# R204B.net
KiCad netlist of a schematic drawn in EAGLE
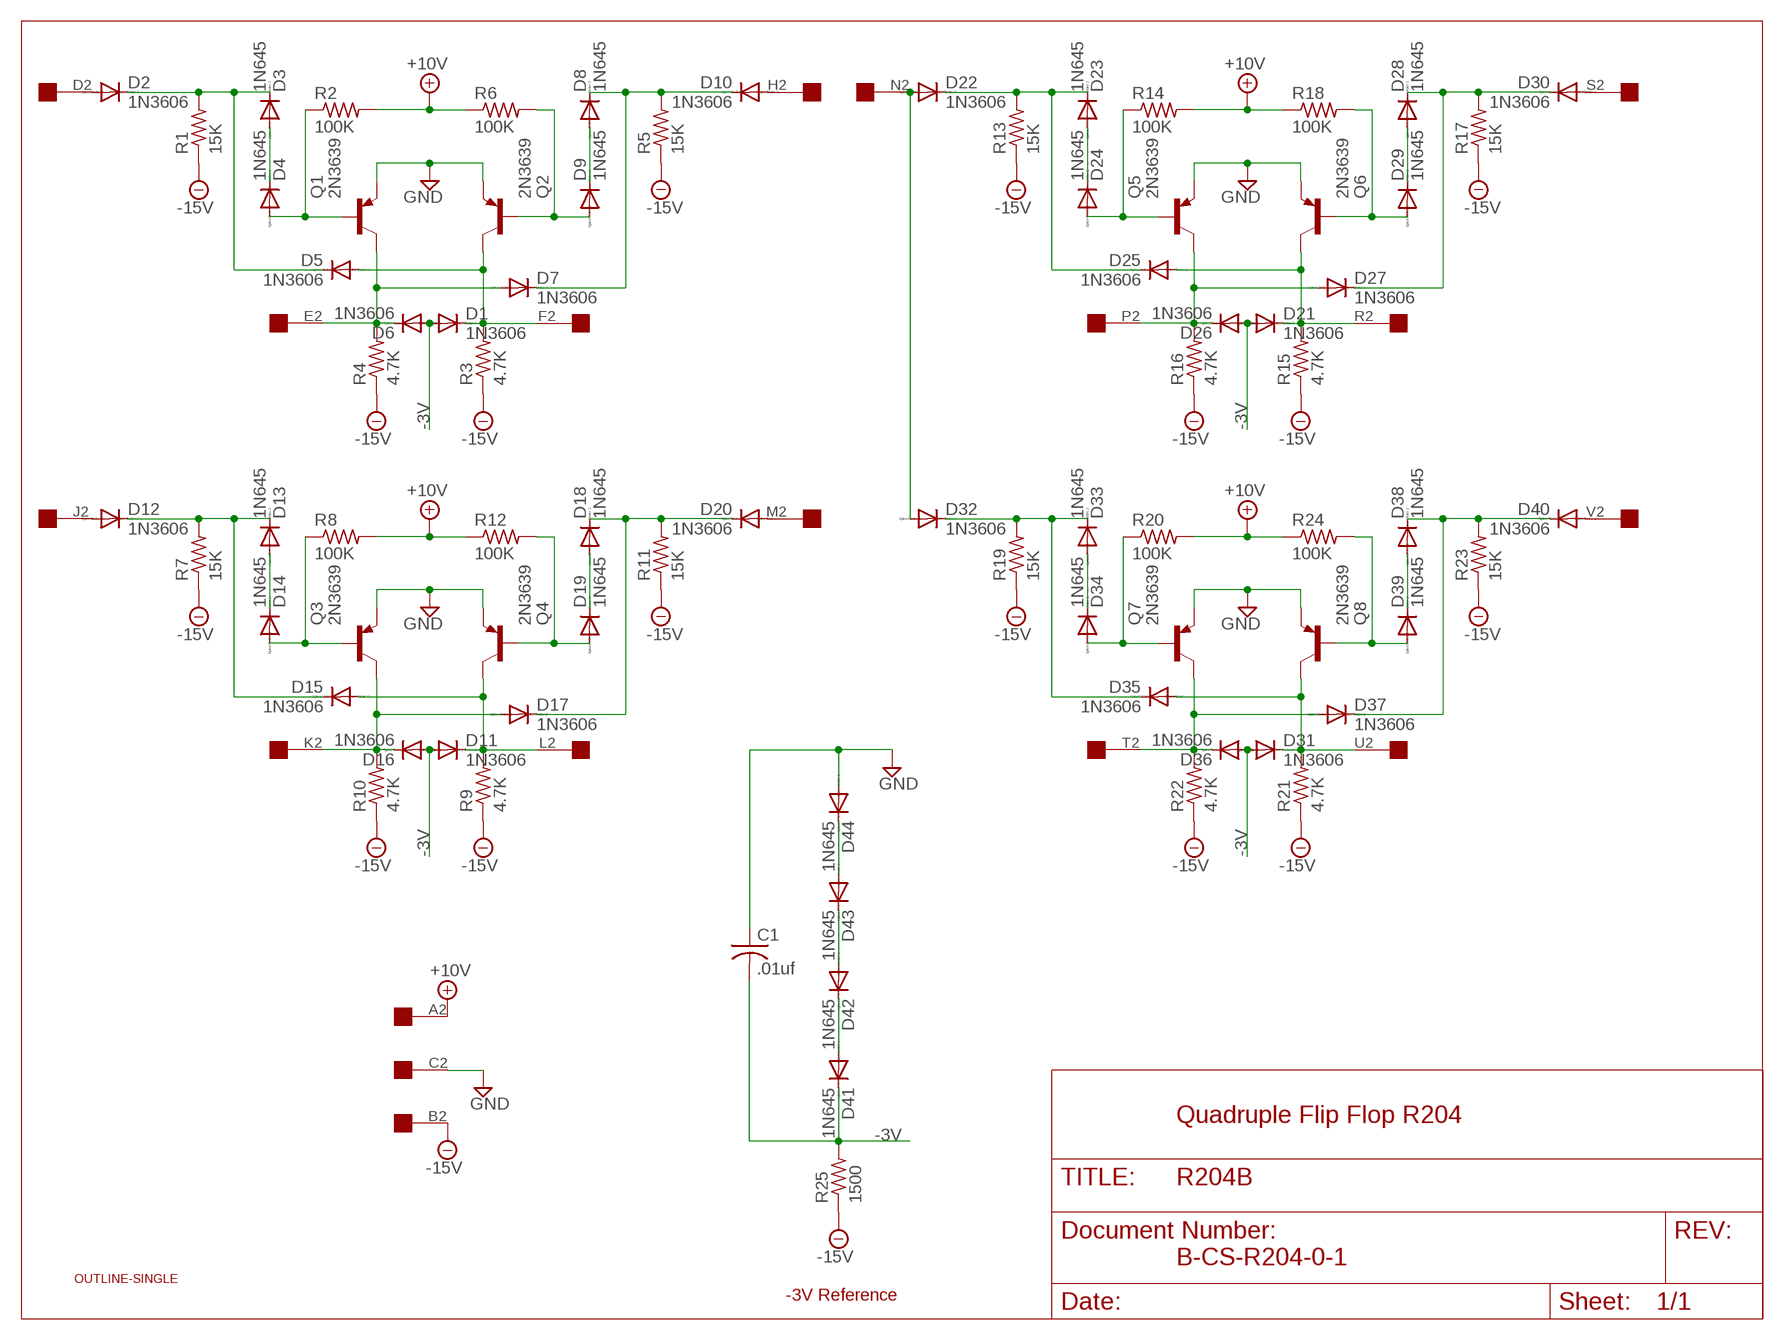
[diagram p0: schematic, sheet 1]

(export (version "E")
  (design (tool "Eeschema 10.0.6"))
  (components
    (comp (ref "C1")
      (value ".01uf")
      (footprint "eagle-import:C050-025X075")
      (libsource (lib "eagle-import") (part "C-US050-025X075"))
    )
    (comp (ref "D1")
      (value "1N3606")
      (footprint "eagle-import:DO35-10")
      (libsource (lib "eagle-import") (part "1N4148DO35-10"))
    )
    (comp (ref "D2")
      (value "1N3606")
      (footprint "eagle-import:DO35-10")
      (libsource (lib "eagle-import") (part "1N4148DO35-10"))
    )
    (comp (ref "D3")
      (value "1N645")
      (footprint "eagle-import:DO35-10")
      (libsource (lib "eagle-import") (part "1N4148DO35-10"))
    )
    (comp (ref "D4")
      (value "1N645")
      (footprint "eagle-import:DO35-10")
      (libsource (lib "eagle-import") (part "1N4148DO35-10"))
    )
    (comp (ref "D5")
      (value "1N3606")
      (footprint "eagle-import:DO35-10")
      (libsource (lib "eagle-import") (part "1N4148DO35-10"))
    )
    (comp (ref "D6")
      (value "1N3606")
      (footprint "eagle-import:DO35-10")
      (libsource (lib "eagle-import") (part "1N4148DO35-10"))
    )
    (comp (ref "D7")
      (value "1N3606")
      (footprint "eagle-import:DO35-10")
      (libsource (lib "eagle-import") (part "1N4148DO35-10"))
    )
    (comp (ref "D8")
      (value "1N645")
      (footprint "eagle-import:DO35-10")
      (libsource (lib "eagle-import") (part "1N4148DO35-10"))
    )
    (comp (ref "D9")
      (value "1N645")
      (footprint "eagle-import:DO35-10")
      (libsource (lib "eagle-import") (part "1N4148DO35-10"))
    )
    (comp (ref "D10")
      (value "1N3606")
      (footprint "eagle-import:DO35-10")
      (libsource (lib "eagle-import") (part "1N4148DO35-10"))
    )
    (comp (ref "D11")
      (value "1N3606")
      (footprint "eagle-import:DO35-10")
      (libsource (lib "eagle-import") (part "1N4148DO35-10"))
    )
    (comp (ref "D12")
      (value "1N3606")
      (footprint "eagle-import:DO35-10")
      (libsource (lib "eagle-import") (part "1N4148DO35-10"))
    )
    (comp (ref "D13")
      (value "1N645")
      (footprint "eagle-import:DO35-10")
      (libsource (lib "eagle-import") (part "1N4148DO35-10"))
    )
    (comp (ref "D14")
      (value "1N645")
      (footprint "eagle-import:DO35-10")
      (libsource (lib "eagle-import") (part "1N4148DO35-10"))
    )
    (comp (ref "D15")
      (value "1N3606")
      (footprint "eagle-import:DO35-10")
      (libsource (lib "eagle-import") (part "1N4148DO35-10"))
    )
    (comp (ref "D16")
      (value "1N3606")
      (footprint "eagle-import:DO35-10")
      (libsource (lib "eagle-import") (part "1N4148DO35-10"))
    )
    (comp (ref "D17")
      (value "1N3606")
      (footprint "eagle-import:DO35-10")
      (libsource (lib "eagle-import") (part "1N4148DO35-10"))
    )
    (comp (ref "D18")
      (value "1N645")
      (footprint "eagle-import:DO35-10")
      (libsource (lib "eagle-import") (part "1N4148DO35-10"))
    )
    (comp (ref "D19")
      (value "1N645")
      (footprint "eagle-import:DO35-10")
      (libsource (lib "eagle-import") (part "1N4148DO35-10"))
    )
    (comp (ref "D20")
      (value "1N3606")
      (footprint "eagle-import:DO35-10")
      (libsource (lib "eagle-import") (part "1N4148DO35-10"))
    )
    (comp (ref "D21")
      (value "1N3606")
      (footprint "eagle-import:DO35-10")
      (libsource (lib "eagle-import") (part "1N4148DO35-10"))
    )
    (comp (ref "D22")
      (value "1N3606")
      (footprint "eagle-import:DO35-10")
      (libsource (lib "eagle-import") (part "1N4148DO35-10"))
    )
    (comp (ref "D23")
      (value "1N645")
      (footprint "eagle-import:DO35-10")
      (libsource (lib "eagle-import") (part "1N4148DO35-10"))
    )
    (comp (ref "D24")
      (value "1N645")
      (footprint "eagle-import:DO35-10")
      (libsource (lib "eagle-import") (part "1N4148DO35-10"))
    )
    (comp (ref "D25")
      (value "1N3606")
      (footprint "eagle-import:DO35-10")
      (libsource (lib "eagle-import") (part "1N4148DO35-10"))
    )
    (comp (ref "D26")
      (value "1N3606")
      (footprint "eagle-import:DO35-10")
      (libsource (lib "eagle-import") (part "1N4148DO35-10"))
    )
    (comp (ref "D27")
      (value "1N3606")
      (footprint "eagle-import:DO35-10")
      (libsource (lib "eagle-import") (part "1N4148DO35-10"))
    )
    (comp (ref "D28")
      (value "1N645")
      (footprint "eagle-import:DO35-10")
      (libsource (lib "eagle-import") (part "1N4148DO35-10"))
    )
    (comp (ref "D29")
      (value "1N645")
      (footprint "eagle-import:DO35-10")
      (libsource (lib "eagle-import") (part "1N4148DO35-10"))
    )
    (comp (ref "D30")
      (value "1N3606")
      (footprint "eagle-import:DO35-10")
      (libsource (lib "eagle-import") (part "1N4148DO35-10"))
    )
    (comp (ref "D31")
      (value "1N3606")
      (footprint "eagle-import:DO35-10")
      (libsource (lib "eagle-import") (part "1N4148DO35-10"))
    )
    (comp (ref "D32")
      (value "1N3606")
      (footprint "eagle-import:DO35-10")
      (libsource (lib "eagle-import") (part "1N4148DO35-10"))
    )
    (comp (ref "D33")
      (value "1N645")
      (footprint "eagle-import:DO35-10")
      (libsource (lib "eagle-import") (part "1N4148DO35-10"))
    )
    (comp (ref "D34")
      (value "1N645")
      (footprint "eagle-import:DO35-10")
      (libsource (lib "eagle-import") (part "1N4148DO35-10"))
    )
    (comp (ref "D35")
      (value "1N3606")
      (footprint "eagle-import:DO35-10")
      (libsource (lib "eagle-import") (part "1N4148DO35-10"))
    )
    (comp (ref "D36")
      (value "1N3606")
      (footprint "eagle-import:DO35-10")
      (libsource (lib "eagle-import") (part "1N4148DO35-10"))
    )
    (comp (ref "D37")
      (value "1N3606")
      (footprint "eagle-import:DO35-10")
      (libsource (lib "eagle-import") (part "1N4148DO35-10"))
    )
    (comp (ref "D38")
      (value "1N645")
      (footprint "eagle-import:DO35-10")
      (libsource (lib "eagle-import") (part "1N4148DO35-10"))
    )
    (comp (ref "D39")
      (value "1N645")
      (footprint "eagle-import:DO35-10")
      (libsource (lib "eagle-import") (part "1N4148DO35-10"))
    )
    (comp (ref "D40")
      (value "1N3606")
      (footprint "eagle-import:DO35-10")
      (libsource (lib "eagle-import") (part "1N4148DO35-10"))
    )
    (comp (ref "D41")
      (value "1N645")
      (footprint "eagle-import:DO35-10")
      (libsource (lib "eagle-import") (part "1N4148DO35-10"))
    )
    (comp (ref "D42")
      (value "1N645")
      (footprint "eagle-import:DO35-10")
      (libsource (lib "eagle-import") (part "1N4148DO35-10"))
    )
    (comp (ref "D43")
      (value "1N645")
      (footprint "eagle-import:DO35-10")
      (libsource (lib "eagle-import") (part "1N4148DO35-10"))
    )
    (comp (ref "D44")
      (value "1N645")
      (footprint "eagle-import:DO35-10")
      (libsource (lib "eagle-import") (part "1N4148DO35-10"))
    )
    (comp (ref "Q1")
      (value "2N3639")
      (footprint "eagle-import:TO39")
      (libsource (lib "eagle-import") (part "2N3637"))
    )
    (comp (ref "Q2")
      (value "2N3639")
      (footprint "eagle-import:TO39")
      (libsource (lib "eagle-import") (part "2N3637"))
    )
    (comp (ref "Q3")
      (value "2N3639")
      (footprint "eagle-import:TO39")
      (libsource (lib "eagle-import") (part "2N3637"))
    )
    (comp (ref "Q4")
      (value "2N3639")
      (footprint "eagle-import:TO39")
      (libsource (lib "eagle-import") (part "2N3637"))
    )
    (comp (ref "Q5")
      (value "2N3639")
      (footprint "eagle-import:TO39")
      (libsource (lib "eagle-import") (part "2N3637"))
    )
    (comp (ref "Q6")
      (value "2N3639")
      (footprint "eagle-import:TO39")
      (libsource (lib "eagle-import") (part "2N3637"))
    )
    (comp (ref "Q7")
      (value "2N3639")
      (footprint "eagle-import:TO39")
      (libsource (lib "eagle-import") (part "2N3637"))
    )
    (comp (ref "Q8")
      (value "2N3639")
      (footprint "eagle-import:TO39")
      (libsource (lib "eagle-import") (part "2N3637"))
    )
    (comp (ref "R1")
      (value "15K")
      (footprint "eagle-import:0207_10")
      (libsource (lib "eagle-import") (part "R-US_0207/10"))
    )
    (comp (ref "R2")
      (value "100K")
      (footprint "eagle-import:0207_10")
      (libsource (lib "eagle-import") (part "R-US_0207/10"))
    )
    (comp (ref "R3")
      (value "4.7K")
      (footprint "eagle-import:0207_10")
      (libsource (lib "eagle-import") (part "R-US_0207/10"))
    )
    (comp (ref "R4")
      (value "4.7K")
      (footprint "eagle-import:0207_10")
      (libsource (lib "eagle-import") (part "R-US_0207/10"))
    )
    (comp (ref "R5")
      (value "15K")
      (footprint "eagle-import:0207_10")
      (libsource (lib "eagle-import") (part "R-US_0207/10"))
    )
    (comp (ref "R6")
      (value "100K")
      (footprint "eagle-import:0207_10")
      (libsource (lib "eagle-import") (part "R-US_0207/10"))
    )
    (comp (ref "R7")
      (value "15K")
      (footprint "eagle-import:0207_10")
      (libsource (lib "eagle-import") (part "R-US_0207/10"))
    )
    (comp (ref "R8")
      (value "100K")
      (footprint "eagle-import:0207_10")
      (libsource (lib "eagle-import") (part "R-US_0207/10"))
    )
    (comp (ref "R9")
      (value "4.7K")
      (footprint "eagle-import:0207_10")
      (libsource (lib "eagle-import") (part "R-US_0207/10"))
    )
    (comp (ref "R10")
      (value "4.7K")
      (footprint "eagle-import:0207_10")
      (libsource (lib "eagle-import") (part "R-US_0207/10"))
    )
    (comp (ref "R11")
      (value "15K")
      (footprint "eagle-import:0207_10")
      (libsource (lib "eagle-import") (part "R-US_0207/10"))
    )
    (comp (ref "R12")
      (value "100K")
      (footprint "eagle-import:0207_10")
      (libsource (lib "eagle-import") (part "R-US_0207/10"))
    )
    (comp (ref "R13")
      (value "15K")
      (footprint "eagle-import:0207_10")
      (libsource (lib "eagle-import") (part "R-US_0207/10"))
    )
    (comp (ref "R14")
      (value "100K")
      (footprint "eagle-import:0207_10")
      (libsource (lib "eagle-import") (part "R-US_0207/10"))
    )
    (comp (ref "R15")
      (value "4.7K")
      (footprint "eagle-import:0207_10")
      (libsource (lib "eagle-import") (part "R-US_0207/10"))
    )
    (comp (ref "R16")
      (value "4.7K")
      (footprint "eagle-import:0207_10")
      (libsource (lib "eagle-import") (part "R-US_0207/10"))
    )
    (comp (ref "R17")
      (value "15K")
      (footprint "eagle-import:0207_10")
      (libsource (lib "eagle-import") (part "R-US_0207/10"))
    )
    (comp (ref "R18")
      (value "100K")
      (footprint "eagle-import:0207_10")
      (libsource (lib "eagle-import") (part "R-US_0207/10"))
    )
    (comp (ref "R19")
      (value "15K")
      (footprint "eagle-import:0207_10")
      (libsource (lib "eagle-import") (part "R-US_0207/10"))
    )
    (comp (ref "R20")
      (value "100K")
      (footprint "eagle-import:0207_10")
      (libsource (lib "eagle-import") (part "R-US_0207/10"))
    )
    (comp (ref "R21")
      (value "4.7K")
      (footprint "eagle-import:0207_10")
      (libsource (lib "eagle-import") (part "R-US_0207/10"))
    )
    (comp (ref "R22")
      (value "4.7K")
      (footprint "eagle-import:0207_10")
      (libsource (lib "eagle-import") (part "R-US_0207/10"))
    )
    (comp (ref "R23")
      (value "15K")
      (footprint "eagle-import:0207_10")
      (libsource (lib "eagle-import") (part "R-US_0207/10"))
    )
    (comp (ref "R24")
      (value "100K")
      (footprint "eagle-import:0207_10")
      (libsource (lib "eagle-import") (part "R-US_0207/10"))
    )
    (comp (ref "R25")
      (value "1500")
      (footprint "eagle-import:0207_10")
      (libsource (lib "eagle-import") (part "R-US_0207/10"))
    )
    (comp (ref "U$1")
      (value "OUTLINE-SINGLE")
      (footprint "eagle-import:SINGLE")
      (libsource (lib "eagle-import") (part "OUTLINE-SINGLE"))
    )
    (comp (ref "U$2")
      (value "EDGE-1")
      (footprint "eagle-import:EDGE-CON1")
      (libsource (lib "eagle-import") (part "EDGE-1"))
    )
  )
  (nets
    (net (code "1") (name "+10V") (class "Default")
      (node (ref "R12") (pin "1") (pinfunction "1_1") (pintype "passive"))
      (node (ref "R14") (pin "2") (pinfunction "2_2") (pintype "passive"))
      (node (ref "R18") (pin "1") (pinfunction "1_1") (pintype "passive"))
      (node (ref "R2") (pin "2") (pinfunction "2_2") (pintype "passive"))
      (node (ref "R20") (pin "2") (pinfunction "2_2") (pintype "passive"))
      (node (ref "R24") (pin "1") (pinfunction "1_1") (pintype "passive"))
      (node (ref "R6") (pin "1") (pinfunction "1_1") (pintype "passive"))
      (node (ref "R8") (pin "2") (pinfunction "2_2") (pintype "passive"))
      (node (ref "U$2") (pin "A2") (pinfunction "1_A2") (pintype "bidirectional"))
    )
    (net (code "2") (name "-15V") (class "Default")
      (node (ref "R1") (pin "1") (pinfunction "1_1") (pintype "passive"))
      (node (ref "R10") (pin "1") (pinfunction "1_1") (pintype "passive"))
      (node (ref "R11") (pin "1") (pinfunction "1_1") (pintype "passive"))
      (node (ref "R13") (pin "1") (pinfunction "1_1") (pintype "passive"))
      (node (ref "R15") (pin "1") (pinfunction "1_1") (pintype "passive"))
      (node (ref "R16") (pin "1") (pinfunction "1_1") (pintype "passive"))
      (node (ref "R17") (pin "1") (pinfunction "1_1") (pintype "passive"))
      (node (ref "R19") (pin "1") (pinfunction "1_1") (pintype "passive"))
      (node (ref "R21") (pin "1") (pinfunction "1_1") (pintype "passive"))
      (node (ref "R22") (pin "1") (pinfunction "1_1") (pintype "passive"))
      (node (ref "R23") (pin "1") (pinfunction "1_1") (pintype "passive"))
      (node (ref "R25") (pin "1") (pinfunction "1_1") (pintype "passive"))
      (node (ref "R3") (pin "1") (pinfunction "1_1") (pintype "passive"))
      (node (ref "R4") (pin "1") (pinfunction "1_1") (pintype "passive"))
      (node (ref "R5") (pin "1") (pinfunction "1_1") (pintype "passive"))
      (node (ref "R7") (pin "1") (pinfunction "1_1") (pintype "passive"))
      (node (ref "R9") (pin "1") (pinfunction "1_1") (pintype "passive"))
      (node (ref "U$2") (pin "B2") (pinfunction "1_B2") (pintype "bidirectional"))
    )
    (net (code "3") (name "/-3V") (class "Default")
      (node (ref "C1") (pin "2") (pinfunction "2_2") (pintype "passive"))
      (node (ref "D1") (pin "A") (pinfunction "A_A") (pintype "passive"))
      (node (ref "D11") (pin "A") (pinfunction "A_A") (pintype "passive"))
      (node (ref "D16") (pin "A") (pinfunction "A_A") (pintype "passive"))
      (node (ref "D21") (pin "A") (pinfunction "A_A") (pintype "passive"))
      (node (ref "D26") (pin "A") (pinfunction "A_A") (pintype "passive"))
      (node (ref "D31") (pin "A") (pinfunction "A_A") (pintype "passive"))
      (node (ref "D36") (pin "A") (pinfunction "A_A") (pintype "passive"))
      (node (ref "D41") (pin "C") (pinfunction "C_C") (pintype "passive"))
      (node (ref "D6") (pin "A") (pinfunction "A_A") (pintype "passive"))
      (node (ref "R25") (pin "2") (pinfunction "2_2") (pintype "passive"))
    )
    (net (code "4") (name "GND") (class "Default")
      (node (ref "C1") (pin "1") (pinfunction "1_1") (pintype "passive"))
      (node (ref "D44") (pin "A") (pinfunction "A_A") (pintype "passive"))
      (node (ref "Q1") (pin "1") (pinfunction "E_1") (pintype "passive"))
      (node (ref "Q2") (pin "1") (pinfunction "E_1") (pintype "passive"))
      (node (ref "Q3") (pin "1") (pinfunction "E_1") (pintype "passive"))
      (node (ref "Q4") (pin "1") (pinfunction "E_1") (pintype "passive"))
      (node (ref "Q5") (pin "1") (pinfunction "E_1") (pintype "passive"))
      (node (ref "Q6") (pin "1") (pinfunction "E_1") (pintype "passive"))
      (node (ref "Q7") (pin "1") (pinfunction "E_1") (pintype "passive"))
      (node (ref "Q8") (pin "1") (pinfunction "E_1") (pintype "passive"))
      (node (ref "U$2") (pin "C2") (pinfunction "1_C2") (pintype "bidirectional"))
    )
    (net (code "5") (name "Net-(D2-PadC)") (class "Default")
      (node (ref "D2") (pin "C") (pinfunction "C_C") (pintype "passive"))
      (node (ref "D3") (pin "C") (pinfunction "C_C") (pintype "passive"))
      (node (ref "D5") (pin "C") (pinfunction "C_C") (pintype "passive"))
      (node (ref "R1") (pin "2") (pinfunction "2_2") (pintype "passive"))
    )
    (net (code "6") (name "Net-(D3-PadA)") (class "Default")
      (node (ref "D3") (pin "A") (pinfunction "A_A") (pintype "passive"))
      (node (ref "D4") (pin "C") (pinfunction "C_C") (pintype "passive"))
    )
    (net (code "7") (name "Net-(D8-PadA)") (class "Default")
      (node (ref "D8") (pin "A") (pinfunction "A_A") (pintype "passive"))
      (node (ref "D9") (pin "C") (pinfunction "C_C") (pintype "passive"))
    )
    (net (code "8") (name "Net-(D10-PadC)") (class "Default")
      (node (ref "D10") (pin "C") (pinfunction "C_C") (pintype "passive"))
      (node (ref "D7") (pin "C") (pinfunction "C_C") (pintype "passive"))
      (node (ref "D8") (pin "C") (pinfunction "C_C") (pintype "passive"))
      (node (ref "R5") (pin "2") (pinfunction "2_2") (pintype "passive"))
    )
    (net (code "9") (name "Net-(D12-PadC)") (class "Default")
      (node (ref "D12") (pin "C") (pinfunction "C_C") (pintype "passive"))
      (node (ref "D13") (pin "C") (pinfunction "C_C") (pintype "passive"))
      (node (ref "D15") (pin "C") (pinfunction "C_C") (pintype "passive"))
      (node (ref "R7") (pin "2") (pinfunction "2_2") (pintype "passive"))
    )
    (net (code "10") (name "Net-(D13-PadA)") (class "Default")
      (node (ref "D13") (pin "A") (pinfunction "A_A") (pintype "passive"))
      (node (ref "D14") (pin "C") (pinfunction "C_C") (pintype "passive"))
    )
    (net (code "11") (name "Net-(D17-PadC)") (class "Default")
      (node (ref "D17") (pin "C") (pinfunction "C_C") (pintype "passive"))
      (node (ref "D18") (pin "C") (pinfunction "C_C") (pintype "passive"))
      (node (ref "D20") (pin "C") (pinfunction "C_C") (pintype "passive"))
      (node (ref "R11") (pin "2") (pinfunction "2_2") (pintype "passive"))
    )
    (net (code "12") (name "Net-(D18-PadA)") (class "Default")
      (node (ref "D18") (pin "A") (pinfunction "A_A") (pintype "passive"))
      (node (ref "D19") (pin "C") (pinfunction "C_C") (pintype "passive"))
    )
    (net (code "13") (name "Net-(D22-PadC)") (class "Default")
      (node (ref "D22") (pin "C") (pinfunction "C_C") (pintype "passive"))
      (node (ref "D23") (pin "C") (pinfunction "C_C") (pintype "passive"))
      (node (ref "D25") (pin "C") (pinfunction "C_C") (pintype "passive"))
      (node (ref "R13") (pin "2") (pinfunction "2_2") (pintype "passive"))
    )
    (net (code "14") (name "Net-(D23-PadA)") (class "Default")
      (node (ref "D23") (pin "A") (pinfunction "A_A") (pintype "passive"))
      (node (ref "D24") (pin "C") (pinfunction "C_C") (pintype "passive"))
    )
    (net (code "15") (name "Net-(D27-PadC)") (class "Default")
      (node (ref "D27") (pin "C") (pinfunction "C_C") (pintype "passive"))
      (node (ref "D28") (pin "C") (pinfunction "C_C") (pintype "passive"))
      (node (ref "D30") (pin "C") (pinfunction "C_C") (pintype "passive"))
      (node (ref "R17") (pin "2") (pinfunction "2_2") (pintype "passive"))
    )
    (net (code "16") (name "Net-(D28-PadA)") (class "Default")
      (node (ref "D28") (pin "A") (pinfunction "A_A") (pintype "passive"))
      (node (ref "D29") (pin "C") (pinfunction "C_C") (pintype "passive"))
    )
    (net (code "17") (name "Net-(D32-PadC)") (class "Default")
      (node (ref "D32") (pin "C") (pinfunction "C_C") (pintype "passive"))
      (node (ref "D33") (pin "C") (pinfunction "C_C") (pintype "passive"))
      (node (ref "D35") (pin "C") (pinfunction "C_C") (pintype "passive"))
      (node (ref "R19") (pin "2") (pinfunction "2_2") (pintype "passive"))
    )
    (net (code "18") (name "Net-(D33-PadA)") (class "Default")
      (node (ref "D33") (pin "A") (pinfunction "A_A") (pintype "passive"))
      (node (ref "D34") (pin "C") (pinfunction "C_C") (pintype "passive"))
    )
    (net (code "19") (name "Net-(D37-PadC)") (class "Default")
      (node (ref "D37") (pin "C") (pinfunction "C_C") (pintype "passive"))
      (node (ref "D38") (pin "C") (pinfunction "C_C") (pintype "passive"))
      (node (ref "D40") (pin "C") (pinfunction "C_C") (pintype "passive"))
      (node (ref "R23") (pin "2") (pinfunction "2_2") (pintype "passive"))
    )
    (net (code "20") (name "Net-(D38-PadA)") (class "Default")
      (node (ref "D38") (pin "A") (pinfunction "A_A") (pintype "passive"))
      (node (ref "D39") (pin "C") (pinfunction "C_C") (pintype "passive"))
    )
    (net (code "21") (name "Net-(D41-PadA)") (class "Default")
      (node (ref "D41") (pin "A") (pinfunction "A_A") (pintype "passive"))
      (node (ref "D42") (pin "C") (pinfunction "C_C") (pintype "passive"))
    )
    (net (code "22") (name "Net-(D42-PadA)") (class "Default")
      (node (ref "D42") (pin "A") (pinfunction "A_A") (pintype "passive"))
      (node (ref "D43") (pin "C") (pinfunction "C_C") (pintype "passive"))
    )
    (net (code "23") (name "Net-(D43-PadA)") (class "Default")
      (node (ref "D43") (pin "A") (pinfunction "A_A") (pintype "passive"))
      (node (ref "D44") (pin "C") (pinfunction "C_C") (pintype "passive"))
    )
    (net (code "24") (name "Net-(Q1-B)") (class "Default")
      (node (ref "D4") (pin "A") (pinfunction "A_A") (pintype "passive"))
      (node (ref "Q1") (pin "2") (pinfunction "B_2") (pintype "passive"))
      (node (ref "R2") (pin "1") (pinfunction "1_1") (pintype "passive"))
    )
    (net (code "25") (name "Net-(Q1-C)") (class "Default")
      (node (ref "D6") (pin "C") (pinfunction "C_C") (pintype "passive"))
      (node (ref "D7") (pin "A") (pinfunction "A_A") (pintype "passive"))
      (node (ref "Q1") (pin "3") (pinfunction "C_3") (pintype "passive"))
      (node (ref "R4") (pin "2") (pinfunction "2_2") (pintype "passive"))
      (node (ref "U$2") (pin "E2") (pinfunction "1_E2") (pintype "bidirectional"))
    )
    (net (code "26") (name "Net-(Q2-B)") (class "Default")
      (node (ref "D9") (pin "A") (pinfunction "A_A") (pintype "passive"))
      (node (ref "Q2") (pin "2") (pinfunction "B_2") (pintype "passive"))
      (node (ref "R6") (pin "2") (pinfunction "2_2") (pintype "passive"))
    )
    (net (code "27") (name "Net-(Q2-C)") (class "Default")
      (node (ref "D1") (pin "C") (pinfunction "C_C") (pintype "passive"))
      (node (ref "D5") (pin "A") (pinfunction "A_A") (pintype "passive"))
      (node (ref "Q2") (pin "3") (pinfunction "C_3") (pintype "passive"))
      (node (ref "R3") (pin "2") (pinfunction "2_2") (pintype "passive"))
      (node (ref "U$2") (pin "F2") (pinfunction "1_F2") (pintype "bidirectional"))
    )
    (net (code "28") (name "Net-(Q3-B)") (class "Default")
      (node (ref "D14") (pin "A") (pinfunction "A_A") (pintype "passive"))
      (node (ref "Q3") (pin "2") (pinfunction "B_2") (pintype "passive"))
      (node (ref "R8") (pin "1") (pinfunction "1_1") (pintype "passive"))
    )
    (net (code "29") (name "Net-(Q3-C)") (class "Default")
      (node (ref "D16") (pin "C") (pinfunction "C_C") (pintype "passive"))
      (node (ref "D17") (pin "A") (pinfunction "A_A") (pintype "passive"))
      (node (ref "Q3") (pin "3") (pinfunction "C_3") (pintype "passive"))
      (node (ref "R10") (pin "2") (pinfunction "2_2") (pintype "passive"))
      (node (ref "U$2") (pin "K2") (pinfunction "1_K2") (pintype "bidirectional"))
    )
    (net (code "30") (name "Net-(Q4-B)") (class "Default")
      (node (ref "D19") (pin "A") (pinfunction "A_A") (pintype "passive"))
      (node (ref "Q4") (pin "2") (pinfunction "B_2") (pintype "passive"))
      (node (ref "R12") (pin "2") (pinfunction "2_2") (pintype "passive"))
    )
    (net (code "31") (name "Net-(Q4-C)") (class "Default")
      (node (ref "D11") (pin "C") (pinfunction "C_C") (pintype "passive"))
      (node (ref "D15") (pin "A") (pinfunction "A_A") (pintype "passive"))
      (node (ref "Q4") (pin "3") (pinfunction "C_3") (pintype "passive"))
      (node (ref "R9") (pin "2") (pinfunction "2_2") (pintype "passive"))
      (node (ref "U$2") (pin "L2") (pinfunction "1_L2") (pintype "bidirectional"))
    )
    (net (code "32") (name "Net-(Q5-B)") (class "Default")
      (node (ref "D24") (pin "A") (pinfunction "A_A") (pintype "passive"))
      (node (ref "Q5") (pin "2") (pinfunction "B_2") (pintype "passive"))
      (node (ref "R14") (pin "1") (pinfunction "1_1") (pintype "passive"))
    )
    (net (code "33") (name "Net-(Q5-C)") (class "Default")
      (node (ref "D26") (pin "C") (pinfunction "C_C") (pintype "passive"))
      (node (ref "D27") (pin "A") (pinfunction "A_A") (pintype "passive"))
      (node (ref "Q5") (pin "3") (pinfunction "C_3") (pintype "passive"))
      (node (ref "R16") (pin "2") (pinfunction "2_2") (pintype "passive"))
      (node (ref "U$2") (pin "P2") (pinfunction "1_P2") (pintype "bidirectional"))
    )
    (net (code "34") (name "Net-(Q6-B)") (class "Default")
      (node (ref "D29") (pin "A") (pinfunction "A_A") (pintype "passive"))
      (node (ref "Q6") (pin "2") (pinfunction "B_2") (pintype "passive"))
      (node (ref "R18") (pin "2") (pinfunction "2_2") (pintype "passive"))
    )
    (net (code "35") (name "Net-(Q6-C)") (class "Default")
      (node (ref "D21") (pin "C") (pinfunction "C_C") (pintype "passive"))
      (node (ref "D25") (pin "A") (pinfunction "A_A") (pintype "passive"))
      (node (ref "Q6") (pin "3") (pinfunction "C_3") (pintype "passive"))
      (node (ref "R15") (pin "2") (pinfunction "2_2") (pintype "passive"))
      (node (ref "U$2") (pin "R2") (pinfunction "1_R2") (pintype "bidirectional"))
    )
    (net (code "36") (name "Net-(Q7-B)") (class "Default")
      (node (ref "D34") (pin "A") (pinfunction "A_A") (pintype "passive"))
      (node (ref "Q7") (pin "2") (pinfunction "B_2") (pintype "passive"))
      (node (ref "R20") (pin "1") (pinfunction "1_1") (pintype "passive"))
    )
    (net (code "37") (name "Net-(Q7-C)") (class "Default")
      (node (ref "D36") (pin "C") (pinfunction "C_C") (pintype "passive"))
      (node (ref "D37") (pin "A") (pinfunction "A_A") (pintype "passive"))
      (node (ref "Q7") (pin "3") (pinfunction "C_3") (pintype "passive"))
      (node (ref "R22") (pin "2") (pinfunction "2_2") (pintype "passive"))
      (node (ref "U$2") (pin "T2") (pinfunction "1_T2") (pintype "bidirectional"))
    )
    (net (code "38") (name "Net-(Q8-B)") (class "Default")
      (node (ref "D39") (pin "A") (pinfunction "A_A") (pintype "passive"))
      (node (ref "Q8") (pin "2") (pinfunction "B_2") (pintype "passive"))
      (node (ref "R24") (pin "2") (pinfunction "2_2") (pintype "passive"))
    )
    (net (code "39") (name "Net-(Q8-C)") (class "Default")
      (node (ref "D31") (pin "C") (pinfunction "C_C") (pintype "passive"))
      (node (ref "D35") (pin "A") (pinfunction "A_A") (pintype "passive"))
      (node (ref "Q8") (pin "3") (pinfunction "C_3") (pintype "passive"))
      (node (ref "R21") (pin "2") (pinfunction "2_2") (pintype "passive"))
      (node (ref "U$2") (pin "U2") (pinfunction "1_U2") (pintype "bidirectional"))
    )
    (net (code "40") (name "Net-(U$2D-1)") (class "Default")
      (node (ref "D2") (pin "A") (pinfunction "A_A") (pintype "passive"))
      (node (ref "U$2") (pin "D2") (pinfunction "1_D2") (pintype "bidirectional"))
    )
    (net (code "41") (name "Net-(U$2G-1)") (class "Default")
      (node (ref "D10") (pin "A") (pinfunction "A_A") (pintype "passive"))
      (node (ref "U$2") (pin "H2") (pinfunction "1_H2") (pintype "bidirectional"))
    )
    (net (code "42") (name "Net-(U$2H-1)") (class "Default")
      (node (ref "D12") (pin "A") (pinfunction "A_A") (pintype "passive"))
      (node (ref "U$2") (pin "J2") (pinfunction "1_J2") (pintype "bidirectional"))
    )
    (net (code "43") (name "Net-(U$2K-1)") (class "Default")
      (node (ref "D20") (pin "A") (pinfunction "A_A") (pintype "passive"))
      (node (ref "U$2") (pin "M2") (pinfunction "1_M2") (pintype "bidirectional"))
    )
    (net (code "44") (name "Net-(U$2L-1)") (class "Default")
      (node (ref "D22") (pin "A") (pinfunction "A_A") (pintype "passive"))
      (node (ref "D32") (pin "A") (pinfunction "A_A") (pintype "passive"))
      (node (ref "U$2") (pin "N2") (pinfunction "1_N2") (pintype "bidirectional"))
    )
    (net (code "45") (name "Net-(U$2O-1)") (class "Default")
      (node (ref "D30") (pin "A") (pinfunction "A_A") (pintype "passive"))
      (node (ref "U$2") (pin "S2") (pinfunction "1_S2") (pintype "bidirectional"))
    )
    (net (code "46") (name "Net-(U$2R-1)") (class "Default")
      (node (ref "D40") (pin "A") (pinfunction "A_A") (pintype "passive"))
      (node (ref "U$2") (pin "V2") (pinfunction "1_V2") (pintype "bidirectional"))
    )
  )
)
